# BOARD_CONNECTOR_1x.net
KiCad netlist of a schematic drawn in Altium Designer
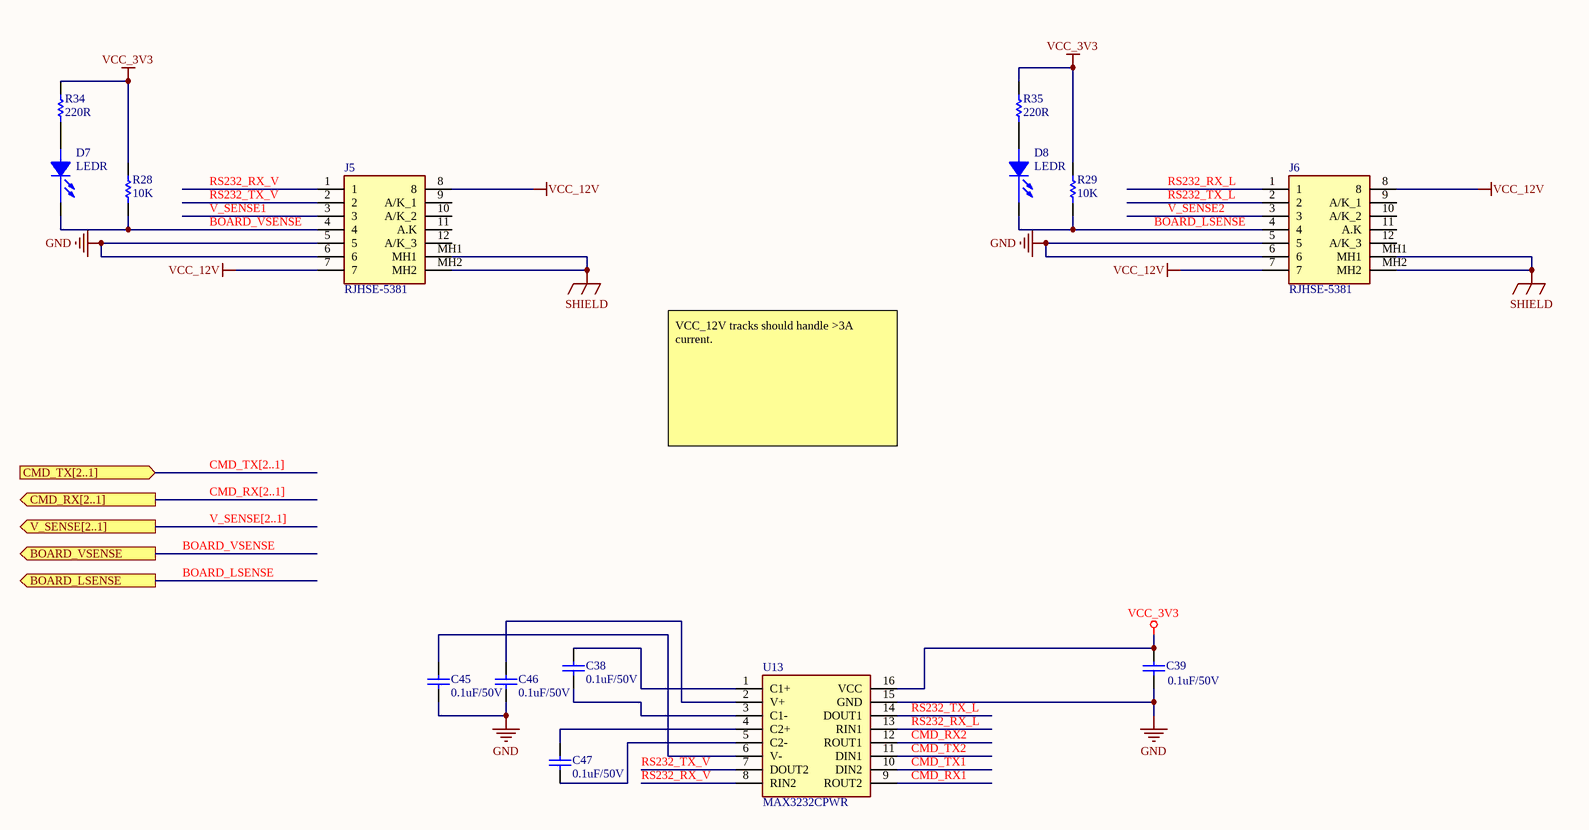
[diagram p0: BOARD_CONNECTOR_1x.SchDoc]

(export (version "E")
  (design (tool "Eeschema 10.0.6"))
  (components
    (comp (ref "C38")
      (value "0.1uF/50V")
      (footprint "0603C")
      (description "Multilayer Ceramic Capacitors MLCC - SMD/SMT 50V 0.1uF 0603 X7R 20%")
      (fields (field (name "MFR") "KEMET") (field (name "MFR PART NO") "C0603C104M5RACTU"))
      (libsource (lib "Miscellaneous Devices") (part "Cap"))
    )
    (comp (ref "C39")
      (value "0.1uF/50V")
      (footprint "0603C")
      (description "Multilayer Ceramic Capacitors MLCC - SMD/SMT 50V 0.1uF 0603 X7R 20%")
      (fields (field (name "MFR") "KEMET") (field (name "MFR PART NO") "C0603C104M5RACTU"))
      (libsource (lib "Miscellaneous Devices") (part "Cap"))
    )
    (comp (ref "C45")
      (value "0.1uF/50V")
      (footprint "0603C")
      (description "Multilayer Ceramic Capacitors MLCC - SMD/SMT 50V 0.1uF 0603 X7R 20%")
      (fields (field (name "MFR") "KEMET") (field (name "MFR PART NO") "C0603C104M5RACTU"))
      (libsource (lib "Miscellaneous Devices") (part "Cap"))
    )
    (comp (ref "C46")
      (value "0.1uF/50V")
      (footprint "0603C")
      (description "Multilayer Ceramic Capacitors MLCC - SMD/SMT 50V 0.1uF 0603 X7R 20%")
      (fields (field (name "MFR") "KEMET") (field (name "MFR PART NO") "C0603C104M5RACTU"))
      (libsource (lib "Miscellaneous Devices") (part "Cap"))
    )
    (comp (ref "C47")
      (value "0.1uF/50V")
      (footprint "0603C")
      (description "Multilayer Ceramic Capacitors MLCC - SMD/SMT 50V 0.1uF 0603 X7R 20%")
      (fields (field (name "MFR") "KEMET") (field (name "MFR PART NO") "C0603C104M5RACTU"))
      (libsource (lib "Miscellaneous Devices") (part "Cap"))
    )
    (comp (ref "D7")
      (value "LEDR")
      (footprint "LED_0603")
      (description "Standard LEDs - SMD Red 631nm 14mcd 5mA")
      (fields (field (name "MFR") "Lite On") (field (name "MFR PART NO") "LTST-C193KRKT-5A"))
      (libsource (lib "de20") (part "LED"))
    )
    (comp (ref "D8")
      (value "LEDR")
      (footprint "LED_0603")
      (description "Standard LEDs - SMD Red 631nm 14mcd 5mA")
      (fields (field (name "MFR") "Lite On") (field (name "MFR PART NO") "LTST-C193KRKT-5A"))
      (libsource (lib "de20") (part "LED"))
    )
    (comp (ref "J5")
      (value "RJHSE-5381")
      (footprint "RJHSE5381")
      (description "Modular Connectors / Ethernet Connectors R/A RJ45 SHEILDED 8 CONT Y/G LEDS")
      (fields
        (field (name "MFR") "Amphenol Commercial Products")
        (field (name "STOCKIEST PART NO") "523-RJHSE-5381")
      )
      (libsource (lib "*") (part "RJHSE-5381"))
    )
    (comp (ref "J6")
      (value "RJHSE-5381")
      (footprint "RJHSE5381")
      (description "Modular Connectors / Ethernet Connectors R/A RJ45 SHEILDED 8 CONT Y/G LEDS")
      (fields
        (field (name "MFR") "Amphenol Commercial Products")
        (field (name "STOCKIEST PART NO") "523-RJHSE-5381")
      )
      (libsource (lib "*") (part "RJHSE-5381"))
    )
    (comp (ref "R28")
      (value "10K")
      (footprint "0603R")
      (description "Thick Film Resistors - SMD 0603 10Kohms 1% Anti-Sulfur AEC-Q200")
      (fields (field (name "MFR") "ROHM Semiconductor") (field (name "MFR PART NO") "SFR03EZPF1002"))
      (libsource (lib "Miscellaneous Devices") (part "Res1"))
    )
    (comp (ref "R29")
      (value "10K")
      (footprint "0603R")
      (description "Thick Film Resistors - SMD 0603 10Kohms 1% Anti-Sulfur AEC-Q200")
      (fields (field (name "MFR") "ROHM Semiconductor") (field (name "MFR PART NO") "SFR03EZPF1002"))
      (libsource (lib "Miscellaneous Devices") (part "Res1"))
    )
    (comp (ref "R34")
      (value "220R")
      (footprint "0603R")
      (description "Thick Film Resistors - SMD 1/10Watt 220ohms 5% Commercial Use")
      (fields (field (name "MFR") "Vishay / Dale") (field (name "MFR PART NO") "CRCW0603220RJNEAC"))
      (libsource (lib "Miscellaneous Devices") (part "Res1"))
    )
    (comp (ref "R35")
      (value "220R")
      (footprint "0603R")
      (description "Thick Film Resistors - SMD 1/10Watt 220ohms 5% Commercial Use")
      (fields (field (name "MFR") "Vishay / Dale") (field (name "MFR PART NO") "CRCW0603220RJNEAC"))
      (libsource (lib "Miscellaneous Devices") (part "Res1"))
    )
    (comp (ref "U13")
      (value "MAX3232CPWR")
      (footprint "MAX3232CPWR")
      (description "RS-232 Interface IC 3-5.5V Mult-Ch RS232")
      (fields (field (name "MFR") "Texas Instruments") (field (name "STOCKIEST PART NO") "595-MAX3232CPWR"))
      (libsource (lib "*") (part "MAX3232CPWR"))
    )
  )
  (nets
    (net (code "1") (name "/BOARD_LSENSE") (class "Default")
      (node (ref "D8") (pin "2") (pinfunction "CATHODE_2") (pintype "passive"))
      (node (ref "J6") (pin "4") (pinfunction "4_4") (pintype "passive"))
      (node (ref "R29") (pin "2") (pinfunction "2_2") (pintype "passive"))
    )
    (net (code "2") (name "/BOARD_VSENSE") (class "Default")
      (node (ref "D7") (pin "2") (pinfunction "CATHODE_2") (pintype "passive"))
      (node (ref "J5") (pin "4") (pinfunction "4_4") (pintype "passive"))
      (node (ref "R28") (pin "2") (pinfunction "2_2") (pintype "passive"))
    )
    (net (code "3") (name "/CMD_RX1") (class "Default")
      (node (ref "U13") (pin "9") (pinfunction "ROUT2_9") (pintype "passive"))
    )
    (net (code "4") (name "/CMD_RX2") (class "Default")
      (node (ref "U13") (pin "12") (pinfunction "ROUT1_12") (pintype "passive"))
    )
    (net (code "6") (name "/CMD_TX1") (class "Default")
      (node (ref "U13") (pin "10") (pinfunction "DIN2_10") (pintype "passive"))
    )
    (net (code "7") (name "/CMD_TX2") (class "Default")
      (node (ref "U13") (pin "11") (pinfunction "DIN1_11") (pintype "passive"))
    )
    (net (code "9") (name "/RS232_RX_L") (class "Default")
      (node (ref "J6") (pin "1") (pinfunction "1_1") (pintype "passive"))
      (node (ref "U13") (pin "13") (pinfunction "RIN1_13") (pintype "passive"))
    )
    (net (code "10") (name "/RS232_RX_V") (class "Default")
      (node (ref "J5") (pin "1") (pinfunction "1_1") (pintype "passive"))
      (node (ref "U13") (pin "8") (pinfunction "RIN2_8") (pintype "passive"))
    )
    (net (code "11") (name "/RS232_TX_L") (class "Default")
      (node (ref "J6") (pin "2") (pinfunction "2_2") (pintype "passive"))
      (node (ref "U13") (pin "14") (pinfunction "DOUT1_14") (pintype "passive"))
    )
    (net (code "12") (name "/RS232_TX_V") (class "Default")
      (node (ref "J5") (pin "2") (pinfunction "2_2") (pintype "passive"))
      (node (ref "U13") (pin "7") (pinfunction "DOUT2_7") (pintype "passive"))
    )
    (net (code "13") (name "/V_SENSE1") (class "Default")
      (node (ref "J5") (pin "3") (pinfunction "3_3") (pintype "passive"))
    )
    (net (code "14") (name "/V_SENSE2") (class "Default")
      (node (ref "J6") (pin "3") (pinfunction "3_3") (pintype "passive"))
    )
    (net (code "16") (name "GND") (class "Default")
      (node (ref "C39") (pin "1") (pinfunction "1_1") (pintype "passive"))
      (node (ref "C45") (pin "1") (pinfunction "1_1") (pintype "passive"))
      (node (ref "C46") (pin "1") (pinfunction "1_1") (pintype "passive"))
      (node (ref "J5") (pin "5") (pinfunction "5_5") (pintype "passive"))
      (node (ref "J5") (pin "6") (pinfunction "6_6") (pintype "passive"))
      (node (ref "J6") (pin "5") (pinfunction "5_5") (pintype "passive"))
      (node (ref "J6") (pin "6") (pinfunction "6_6") (pintype "passive"))
      (node (ref "U13") (pin "15") (pinfunction "GND_15") (pintype "passive"))
    )
    (net (code "17") (name "Net-(D7-ANODE)") (class "Default")
      (node (ref "D7") (pin "1") (pinfunction "ANODE_1") (pintype "passive"))
      (node (ref "R34") (pin "1") (pinfunction "1_1") (pintype "passive"))
    )
    (net (code "18") (name "Net-(D8-ANODE)") (class "Default")
      (node (ref "D8") (pin "1") (pinfunction "ANODE_1") (pintype "passive"))
      (node (ref "R35") (pin "1") (pinfunction "1_1") (pintype "passive"))
    )
    (net (code "19") (name "Net-(U13-C1+)") (class "Default")
      (node (ref "C38") (pin "2") (pinfunction "2_2") (pintype "passive"))
      (node (ref "U13") (pin "1") (pinfunction "C1+_1") (pintype "passive"))
    )
    (net (code "20") (name "Net-(U13-C1-)") (class "Default")
      (node (ref "C38") (pin "1") (pinfunction "1_1") (pintype "passive"))
      (node (ref "U13") (pin "3") (pinfunction "C1-_3") (pintype "passive"))
    )
    (net (code "21") (name "Net-(U13-C2+)") (class "Default")
      (node (ref "C47") (pin "2") (pinfunction "2_2") (pintype "passive"))
      (node (ref "U13") (pin "4") (pinfunction "C2+_4") (pintype "passive"))
    )
    (net (code "22") (name "Net-(U13-C2-)") (class "Default")
      (node (ref "C47") (pin "1") (pinfunction "1_1") (pintype "passive"))
      (node (ref "U13") (pin "5") (pinfunction "C2-_5") (pintype "passive"))
    )
    (net (code "23") (name "Net-(U13-V+)") (class "Default")
      (node (ref "C46") (pin "2") (pinfunction "2_2") (pintype "passive"))
      (node (ref "U13") (pin "2") (pinfunction "V+_2") (pintype "passive"))
    )
    (net (code "24") (name "Net-(U13-V-)") (class "Default")
      (node (ref "C45") (pin "2") (pinfunction "2_2") (pintype "passive"))
      (node (ref "U13") (pin "6") (pinfunction "V-_6") (pintype "passive"))
    )
    (net (code "25") (name "SHIELD") (class "Default")
      (node (ref "J5") (pin "MH1") (pinfunction "MH1_MH1") (pintype "passive"))
      (node (ref "J5") (pin "MH2") (pinfunction "MH2_MH2") (pintype "passive"))
      (node (ref "J6") (pin "MH1") (pinfunction "MH1_MH1") (pintype "passive"))
      (node (ref "J6") (pin "MH2") (pinfunction "MH2_MH2") (pintype "passive"))
    )
    (net (code "26") (name "VCC_3V3") (class "Default")
      (node (ref "C39") (pin "2") (pinfunction "2_2") (pintype "passive"))
      (node (ref "R28") (pin "1") (pinfunction "1_1") (pintype "passive"))
      (node (ref "R29") (pin "1") (pinfunction "1_1") (pintype "passive"))
      (node (ref "R34") (pin "2") (pinfunction "2_2") (pintype "passive"))
      (node (ref "R35") (pin "2") (pinfunction "2_2") (pintype "passive"))
      (node (ref "U13") (pin "16") (pinfunction "VCC_16") (pintype "passive"))
    )
    (net (code "27") (name "VCC_12V") (class "Default")
      (node (ref "J5") (pin "7") (pinfunction "7_7") (pintype "passive"))
      (node (ref "J5") (pin "8") (pinfunction "8_8") (pintype "passive"))
      (node (ref "J6") (pin "7") (pinfunction "7_7") (pintype "passive"))
      (node (ref "J6") (pin "8") (pinfunction "8_8") (pintype "passive"))
    )
    (net (code "28") (name "unconnected-(J5-A.K-Pad11)") (class "Default")
      (node (ref "J5") (pin "11") (pinfunction "A.K_11") (pintype "passive"))
    )
    (net (code "29") (name "unconnected-(J5-A{slash}K_1-Pad9)") (class "Default")
      (node (ref "J5") (pin "9") (pinfunction "A/K_1_9") (pintype "passive"))
    )
    (net (code "30") (name "unconnected-(J5-A{slash}K_2-Pad10)") (class "Default")
      (node (ref "J5") (pin "10") (pinfunction "A/K_2_10") (pintype "passive"))
    )
    (net (code "31") (name "unconnected-(J5-A{slash}K_3-Pad12)") (class "Default")
      (node (ref "J5") (pin "12") (pinfunction "A/K_3_12") (pintype "passive"))
    )
    (net (code "32") (name "unconnected-(J6-A.K-Pad11)") (class "Default")
      (node (ref "J6") (pin "11") (pinfunction "A.K_11") (pintype "passive"))
    )
    (net (code "33") (name "unconnected-(J6-A{slash}K_1-Pad9)") (class "Default")
      (node (ref "J6") (pin "9") (pinfunction "A/K_1_9") (pintype "passive"))
    )
    (net (code "34") (name "unconnected-(J6-A{slash}K_2-Pad10)") (class "Default")
      (node (ref "J6") (pin "10") (pinfunction "A/K_2_10") (pintype "passive"))
    )
    (net (code "35") (name "unconnected-(J6-A{slash}K_3-Pad12)") (class "Default")
      (node (ref "J6") (pin "12") (pinfunction "A/K_3_12") (pintype "passive"))
    )
  )
)
